# OutputModule.net
KiCad netlist of a schematic drawn in EAGLE
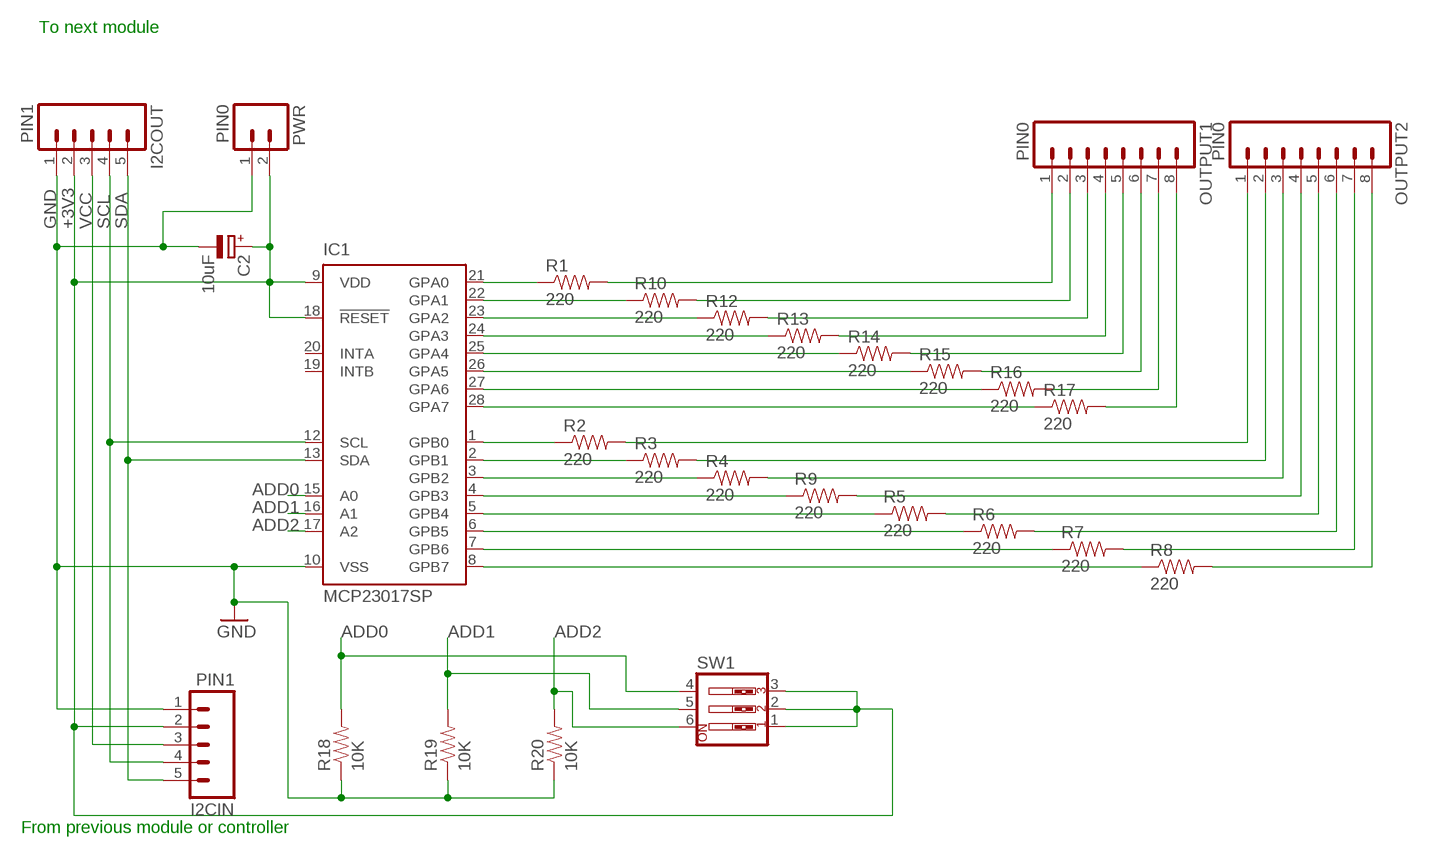
[diagram p0: schematic, sheet 1]

(export (version "E")
  (design (tool "Eeschema 10.0.6"))
  (components
    (comp (ref "C2")
      (value "10uF")
      (footprint "eagle-import:E2,5-6")
      (libsource (lib "eagle-import") (part "CPOL-EUE2.5-6"))
    )
    (comp (ref "I2CIN")
      (value "PIN1")
      (footprint "eagle-import:05P")
      (libsource (lib "eagle-import") (part "M05"))
    )
    (comp (ref "I2COUT")
      (value "PIN1")
      (footprint "eagle-import:05P")
      (libsource (lib "eagle-import") (part "M05"))
    )
    (comp (ref "IC1")
      (value "MCP23017SP")
      (footprint "eagle-import:DIL28-3")
      (fields (field (name "MF") "MICROCHIP") (field (name "MPN") "MCP23017-E/SP"))
      (libsource (lib "eagle-import") (part "MCP23017SP"))
    )
    (comp (ref "OUTPUT1")
      (value "PIN0")
      (footprint "eagle-import:1X08_ROUND")
      (libsource (lib "eagle-import") (part "M08"))
    )
    (comp (ref "OUTPUT2")
      (value "PIN0")
      (footprint "eagle-import:1X08_ROUND")
      (libsource (lib "eagle-import") (part "M08"))
    )
    (comp (ref "PWR")
      (value "PIN0")
      (footprint "eagle-import:02P")
      (libsource (lib "eagle-import") (part "M02"))
    )
    (comp (ref "R1")
      (value "220")
      (footprint "eagle-import:AXIAL-0.4")
      (libsource (lib "eagle-import") (part "RESISTORPTH-1/4W"))
    )
    (comp (ref "R2")
      (value "220")
      (footprint "eagle-import:AXIAL-0.4")
      (libsource (lib "eagle-import") (part "RESISTORPTH-1/4W"))
    )
    (comp (ref "R3")
      (value "220")
      (footprint "eagle-import:AXIAL-0.4")
      (libsource (lib "eagle-import") (part "RESISTORPTH-1/4W"))
    )
    (comp (ref "R4")
      (value "220")
      (footprint "eagle-import:AXIAL-0.4")
      (libsource (lib "eagle-import") (part "RESISTORPTH-1/4W"))
    )
    (comp (ref "R5")
      (value "220")
      (footprint "eagle-import:AXIAL-0.4")
      (libsource (lib "eagle-import") (part "RESISTORPTH-1/4W"))
    )
    (comp (ref "R6")
      (value "220")
      (footprint "eagle-import:AXIAL-0.4")
      (libsource (lib "eagle-import") (part "RESISTORPTH-1/4W"))
    )
    (comp (ref "R7")
      (value "220")
      (footprint "eagle-import:AXIAL-0.4")
      (libsource (lib "eagle-import") (part "RESISTORPTH-1/4W"))
    )
    (comp (ref "R8")
      (value "220")
      (footprint "eagle-import:AXIAL-0.4")
      (libsource (lib "eagle-import") (part "RESISTORPTH-1/4W"))
    )
    (comp (ref "R9")
      (value "220")
      (footprint "eagle-import:AXIAL-0.4")
      (libsource (lib "eagle-import") (part "RESISTORPTH-1/4W"))
    )
    (comp (ref "R10")
      (value "220")
      (footprint "eagle-import:AXIAL-0.4")
      (libsource (lib "eagle-import") (part "RESISTORPTH-1/4W"))
    )
    (comp (ref "R12")
      (value "220")
      (footprint "eagle-import:AXIAL-0.4")
      (libsource (lib "eagle-import") (part "RESISTORPTH-1/4W"))
    )
    (comp (ref "R13")
      (value "220")
      (footprint "eagle-import:AXIAL-0.4")
      (libsource (lib "eagle-import") (part "RESISTORPTH-1/4W"))
    )
    (comp (ref "R14")
      (value "220")
      (footprint "eagle-import:AXIAL-0.4")
      (libsource (lib "eagle-import") (part "RESISTORPTH-1/4W"))
    )
    (comp (ref "R15")
      (value "220")
      (footprint "eagle-import:AXIAL-0.4")
      (libsource (lib "eagle-import") (part "RESISTORPTH-1/4W"))
    )
    (comp (ref "R16")
      (value "220")
      (footprint "eagle-import:AXIAL-0.4")
      (libsource (lib "eagle-import") (part "RESISTORPTH-1/4W"))
    )
    (comp (ref "R17")
      (value "220")
      (footprint "eagle-import:AXIAL-0.4")
      (libsource (lib "eagle-import") (part "RESISTORPTH-1/4W"))
    )
    (comp (ref "R18")
      (value "10K")
      (footprint "eagle-import:AXIAL-0.4")
      (libsource (lib "eagle-import") (part "RESISTORPTH-1/4W"))
    )
    (comp (ref "R19")
      (value "10K")
      (footprint "eagle-import:AXIAL-0.4")
      (libsource (lib "eagle-import") (part "RESISTORPTH-1/4W"))
    )
    (comp (ref "R20")
      (value "10K")
      (footprint "eagle-import:AXIAL-0.4")
      (libsource (lib "eagle-import") (part "RESISTORPTH-1/4W"))
    )
    (comp (ref "SW1")
      (value "SW_DIP-3")
      (footprint "eagle-import:EDG-03")
      (libsource (lib "eagle-import") (part "SW_DIP-3"))
    )
  )
  (nets
    (net (code "1") (name "/+3V3") (class "Default")
      (node (ref "C2") (pin "+") (pinfunction "+_+") (pintype "passive"))
      (node (ref "I2CIN") (pin "2") (pinfunction "2_2") (pintype "passive"))
      (node (ref "I2COUT") (pin "2") (pinfunction "2_2") (pintype "passive"))
      (node (ref "IC1") (pin "18") (pinfunction "~{RESET}_18") (pintype "input"))
      (node (ref "IC1") (pin "9") (pinfunction "VDD_9") (pintype "power_in"))
      (node (ref "PWR") (pin "2") (pinfunction "2_2") (pintype "passive"))
      (node (ref "SW1") (pin "1") (pinfunction "1_1") (pintype "passive"))
      (node (ref "SW1") (pin "2") (pinfunction "2_2") (pintype "passive"))
      (node (ref "SW1") (pin "3") (pinfunction "3_3") (pintype "passive"))
    )
    (net (code "2") (name "/ADD0") (class "Default")
      (node (ref "IC1") (pin "15") (pinfunction "A0_15") (pintype "input"))
      (node (ref "R18") (pin "P$2") (pinfunction "2_P$2") (pintype "passive"))
      (node (ref "SW1") (pin "4") (pinfunction "4_4") (pintype "passive"))
    )
    (net (code "3") (name "/ADD1") (class "Default")
      (node (ref "IC1") (pin "16") (pinfunction "A1_16") (pintype "input"))
      (node (ref "R19") (pin "P$2") (pinfunction "2_P$2") (pintype "passive"))
      (node (ref "SW1") (pin "5") (pinfunction "5_5") (pintype "passive"))
    )
    (net (code "4") (name "/ADD2") (class "Default")
      (node (ref "IC1") (pin "17") (pinfunction "A2_17") (pintype "input"))
      (node (ref "R20") (pin "P$2") (pinfunction "2_P$2") (pintype "passive"))
      (node (ref "SW1") (pin "6") (pinfunction "6_6") (pintype "passive"))
    )
    (net (code "5") (name "/SCL") (class "Default")
      (node (ref "I2CIN") (pin "4") (pinfunction "4_4") (pintype "passive"))
      (node (ref "I2COUT") (pin "4") (pinfunction "4_4") (pintype "passive"))
      (node (ref "IC1") (pin "12") (pinfunction "SCL_12") (pintype "input"))
    )
    (net (code "6") (name "/SDA") (class "Default")
      (node (ref "I2CIN") (pin "5") (pinfunction "5_5") (pintype "passive"))
      (node (ref "I2COUT") (pin "5") (pinfunction "5_5") (pintype "passive"))
      (node (ref "IC1") (pin "13") (pinfunction "SDA_13") (pintype "bidirectional"))
    )
    (net (code "7") (name "/VCC") (class "Default")
      (node (ref "I2CIN") (pin "3") (pinfunction "3_3") (pintype "passive"))
      (node (ref "I2COUT") (pin "3") (pinfunction "3_3") (pintype "passive"))
    )
    (net (code "8") (name "GND") (class "Default")
      (node (ref "C2") (pin "-") (pinfunction "-_-") (pintype "passive"))
      (node (ref "I2CIN") (pin "1") (pinfunction "1_1") (pintype "passive"))
      (node (ref "I2COUT") (pin "1") (pinfunction "1_1") (pintype "passive"))
      (node (ref "IC1") (pin "10") (pinfunction "VSS_10") (pintype "power_in"))
      (node (ref "PWR") (pin "1") (pinfunction "1_1") (pintype "passive"))
      (node (ref "R18") (pin "P$1") (pinfunction "1_P$1") (pintype "passive"))
      (node (ref "R19") (pin "P$1") (pinfunction "1_P$1") (pintype "passive"))
      (node (ref "R20") (pin "P$1") (pinfunction "1_P$1") (pintype "passive"))
    )
    (net (code "9") (name "Net-(IC1-GPA0)") (class "Default")
      (node (ref "IC1") (pin "21") (pinfunction "GPA0_21") (pintype "bidirectional"))
      (node (ref "R1") (pin "P$1") (pinfunction "1_P$1") (pintype "passive"))
    )
    (net (code "10") (name "Net-(IC1-GPA1)") (class "Default")
      (node (ref "IC1") (pin "22") (pinfunction "GPA1_22") (pintype "bidirectional"))
      (node (ref "R10") (pin "P$1") (pinfunction "1_P$1") (pintype "passive"))
    )
    (net (code "11") (name "Net-(IC1-GPA2)") (class "Default")
      (node (ref "IC1") (pin "23") (pinfunction "GPA2_23") (pintype "bidirectional"))
      (node (ref "R12") (pin "P$1") (pinfunction "1_P$1") (pintype "passive"))
    )
    (net (code "12") (name "Net-(IC1-GPA3)") (class "Default")
      (node (ref "IC1") (pin "24") (pinfunction "GPA3_24") (pintype "bidirectional"))
      (node (ref "R13") (pin "P$1") (pinfunction "1_P$1") (pintype "passive"))
    )
    (net (code "13") (name "Net-(IC1-GPA4)") (class "Default")
      (node (ref "IC1") (pin "25") (pinfunction "GPA4_25") (pintype "bidirectional"))
      (node (ref "R14") (pin "P$1") (pinfunction "1_P$1") (pintype "passive"))
    )
    (net (code "14") (name "Net-(IC1-GPA5)") (class "Default")
      (node (ref "IC1") (pin "26") (pinfunction "GPA5_26") (pintype "bidirectional"))
      (node (ref "R15") (pin "P$1") (pinfunction "1_P$1") (pintype "passive"))
    )
    (net (code "15") (name "Net-(IC1-GPA6)") (class "Default")
      (node (ref "IC1") (pin "27") (pinfunction "GPA6_27") (pintype "bidirectional"))
      (node (ref "R16") (pin "P$1") (pinfunction "1_P$1") (pintype "passive"))
    )
    (net (code "16") (name "Net-(IC1-GPA7)") (class "Default")
      (node (ref "IC1") (pin "28") (pinfunction "GPA7_28") (pintype "bidirectional"))
      (node (ref "R17") (pin "P$1") (pinfunction "1_P$1") (pintype "passive"))
    )
    (net (code "17") (name "Net-(IC1-GPB0)") (class "Default")
      (node (ref "IC1") (pin "1") (pinfunction "GPB0_1") (pintype "bidirectional"))
      (node (ref "R2") (pin "P$1") (pinfunction "1_P$1") (pintype "passive"))
    )
    (net (code "18") (name "Net-(IC1-GPB1)") (class "Default")
      (node (ref "IC1") (pin "2") (pinfunction "GPB1_2") (pintype "bidirectional"))
      (node (ref "R3") (pin "P$1") (pinfunction "1_P$1") (pintype "passive"))
    )
    (net (code "19") (name "Net-(IC1-GPB2)") (class "Default")
      (node (ref "IC1") (pin "3") (pinfunction "GPB2_3") (pintype "bidirectional"))
      (node (ref "R4") (pin "P$1") (pinfunction "1_P$1") (pintype "passive"))
    )
    (net (code "20") (name "Net-(IC1-GPB3)") (class "Default")
      (node (ref "IC1") (pin "4") (pinfunction "GPB3_4") (pintype "bidirectional"))
      (node (ref "R9") (pin "P$1") (pinfunction "1_P$1") (pintype "passive"))
    )
    (net (code "21") (name "Net-(IC1-GPB4)") (class "Default")
      (node (ref "IC1") (pin "5") (pinfunction "GPB4_5") (pintype "bidirectional"))
      (node (ref "R5") (pin "P$1") (pinfunction "1_P$1") (pintype "passive"))
    )
    (net (code "22") (name "Net-(IC1-GPB5)") (class "Default")
      (node (ref "IC1") (pin "6") (pinfunction "GPB5_6") (pintype "bidirectional"))
      (node (ref "R6") (pin "P$1") (pinfunction "1_P$1") (pintype "passive"))
    )
    (net (code "23") (name "Net-(IC1-GPB6)") (class "Default")
      (node (ref "IC1") (pin "7") (pinfunction "GPB6_7") (pintype "bidirectional"))
      (node (ref "R7") (pin "P$1") (pinfunction "1_P$1") (pintype "passive"))
    )
    (net (code "24") (name "Net-(IC1-GPB7)") (class "Default")
      (node (ref "IC1") (pin "8") (pinfunction "GPB7_8") (pintype "bidirectional"))
      (node (ref "R8") (pin "P$1") (pinfunction "1_P$1") (pintype "passive"))
    )
    (net (code "25") (name "Net-(R1-2)") (class "Default")
      (node (ref "OUTPUT1") (pin "1") (pinfunction "1_1") (pintype "passive"))
      (node (ref "R1") (pin "P$2") (pinfunction "2_P$2") (pintype "passive"))
    )
    (net (code "26") (name "Net-(R2-2)") (class "Default")
      (node (ref "OUTPUT2") (pin "1") (pinfunction "1_1") (pintype "passive"))
      (node (ref "R2") (pin "P$2") (pinfunction "2_P$2") (pintype "passive"))
    )
    (net (code "27") (name "Net-(R3-2)") (class "Default")
      (node (ref "OUTPUT2") (pin "2") (pinfunction "2_2") (pintype "passive"))
      (node (ref "R3") (pin "P$2") (pinfunction "2_P$2") (pintype "passive"))
    )
    (net (code "28") (name "Net-(R4-2)") (class "Default")
      (node (ref "OUTPUT2") (pin "3") (pinfunction "3_3") (pintype "passive"))
      (node (ref "R4") (pin "P$2") (pinfunction "2_P$2") (pintype "passive"))
    )
    (net (code "29") (name "Net-(R5-2)") (class "Default")
      (node (ref "OUTPUT2") (pin "5") (pinfunction "5_5") (pintype "passive"))
      (node (ref "R5") (pin "P$2") (pinfunction "2_P$2") (pintype "passive"))
    )
    (net (code "30") (name "Net-(R6-2)") (class "Default")
      (node (ref "OUTPUT2") (pin "6") (pinfunction "6_6") (pintype "passive"))
      (node (ref "R6") (pin "P$2") (pinfunction "2_P$2") (pintype "passive"))
    )
    (net (code "31") (name "Net-(R7-2)") (class "Default")
      (node (ref "OUTPUT2") (pin "7") (pinfunction "7_7") (pintype "passive"))
      (node (ref "R7") (pin "P$2") (pinfunction "2_P$2") (pintype "passive"))
    )
    (net (code "32") (name "Net-(R8-2)") (class "Default")
      (node (ref "OUTPUT2") (pin "8") (pinfunction "8_8") (pintype "passive"))
      (node (ref "R8") (pin "P$2") (pinfunction "2_P$2") (pintype "passive"))
    )
    (net (code "33") (name "Net-(R9-2)") (class "Default")
      (node (ref "OUTPUT2") (pin "4") (pinfunction "4_4") (pintype "passive"))
      (node (ref "R9") (pin "P$2") (pinfunction "2_P$2") (pintype "passive"))
    )
    (net (code "34") (name "Net-(R10-2)") (class "Default")
      (node (ref "OUTPUT1") (pin "2") (pinfunction "2_2") (pintype "passive"))
      (node (ref "R10") (pin "P$2") (pinfunction "2_P$2") (pintype "passive"))
    )
    (net (code "35") (name "Net-(R12-2)") (class "Default")
      (node (ref "OUTPUT1") (pin "3") (pinfunction "3_3") (pintype "passive"))
      (node (ref "R12") (pin "P$2") (pinfunction "2_P$2") (pintype "passive"))
    )
    (net (code "36") (name "Net-(R13-2)") (class "Default")
      (node (ref "OUTPUT1") (pin "4") (pinfunction "4_4") (pintype "passive"))
      (node (ref "R13") (pin "P$2") (pinfunction "2_P$2") (pintype "passive"))
    )
    (net (code "37") (name "Net-(R14-2)") (class "Default")
      (node (ref "OUTPUT1") (pin "5") (pinfunction "5_5") (pintype "passive"))
      (node (ref "R14") (pin "P$2") (pinfunction "2_P$2") (pintype "passive"))
    )
    (net (code "38") (name "Net-(R15-2)") (class "Default")
      (node (ref "OUTPUT1") (pin "6") (pinfunction "6_6") (pintype "passive"))
      (node (ref "R15") (pin "P$2") (pinfunction "2_P$2") (pintype "passive"))
    )
    (net (code "39") (name "Net-(R16-2)") (class "Default")
      (node (ref "OUTPUT1") (pin "7") (pinfunction "7_7") (pintype "passive"))
      (node (ref "R16") (pin "P$2") (pinfunction "2_P$2") (pintype "passive"))
    )
    (net (code "40") (name "Net-(R17-2)") (class "Default")
      (node (ref "OUTPUT1") (pin "8") (pinfunction "8_8") (pintype "passive"))
      (node (ref "R17") (pin "P$2") (pinfunction "2_P$2") (pintype "passive"))
    )
    (net (code "41") (name "unconnected-(IC1-INTA-Pad20)") (class "Default")
      (node (ref "IC1") (pin "20") (pinfunction "INTA_20") (pintype "output"))
    )
    (net (code "42") (name "unconnected-(IC1-INTB-Pad19)") (class "Default")
      (node (ref "IC1") (pin "19") (pinfunction "INTB_19") (pintype "output"))
    )
  )
)
